# reva.net
KiCad netlist of a schematic drawn in EAGLE
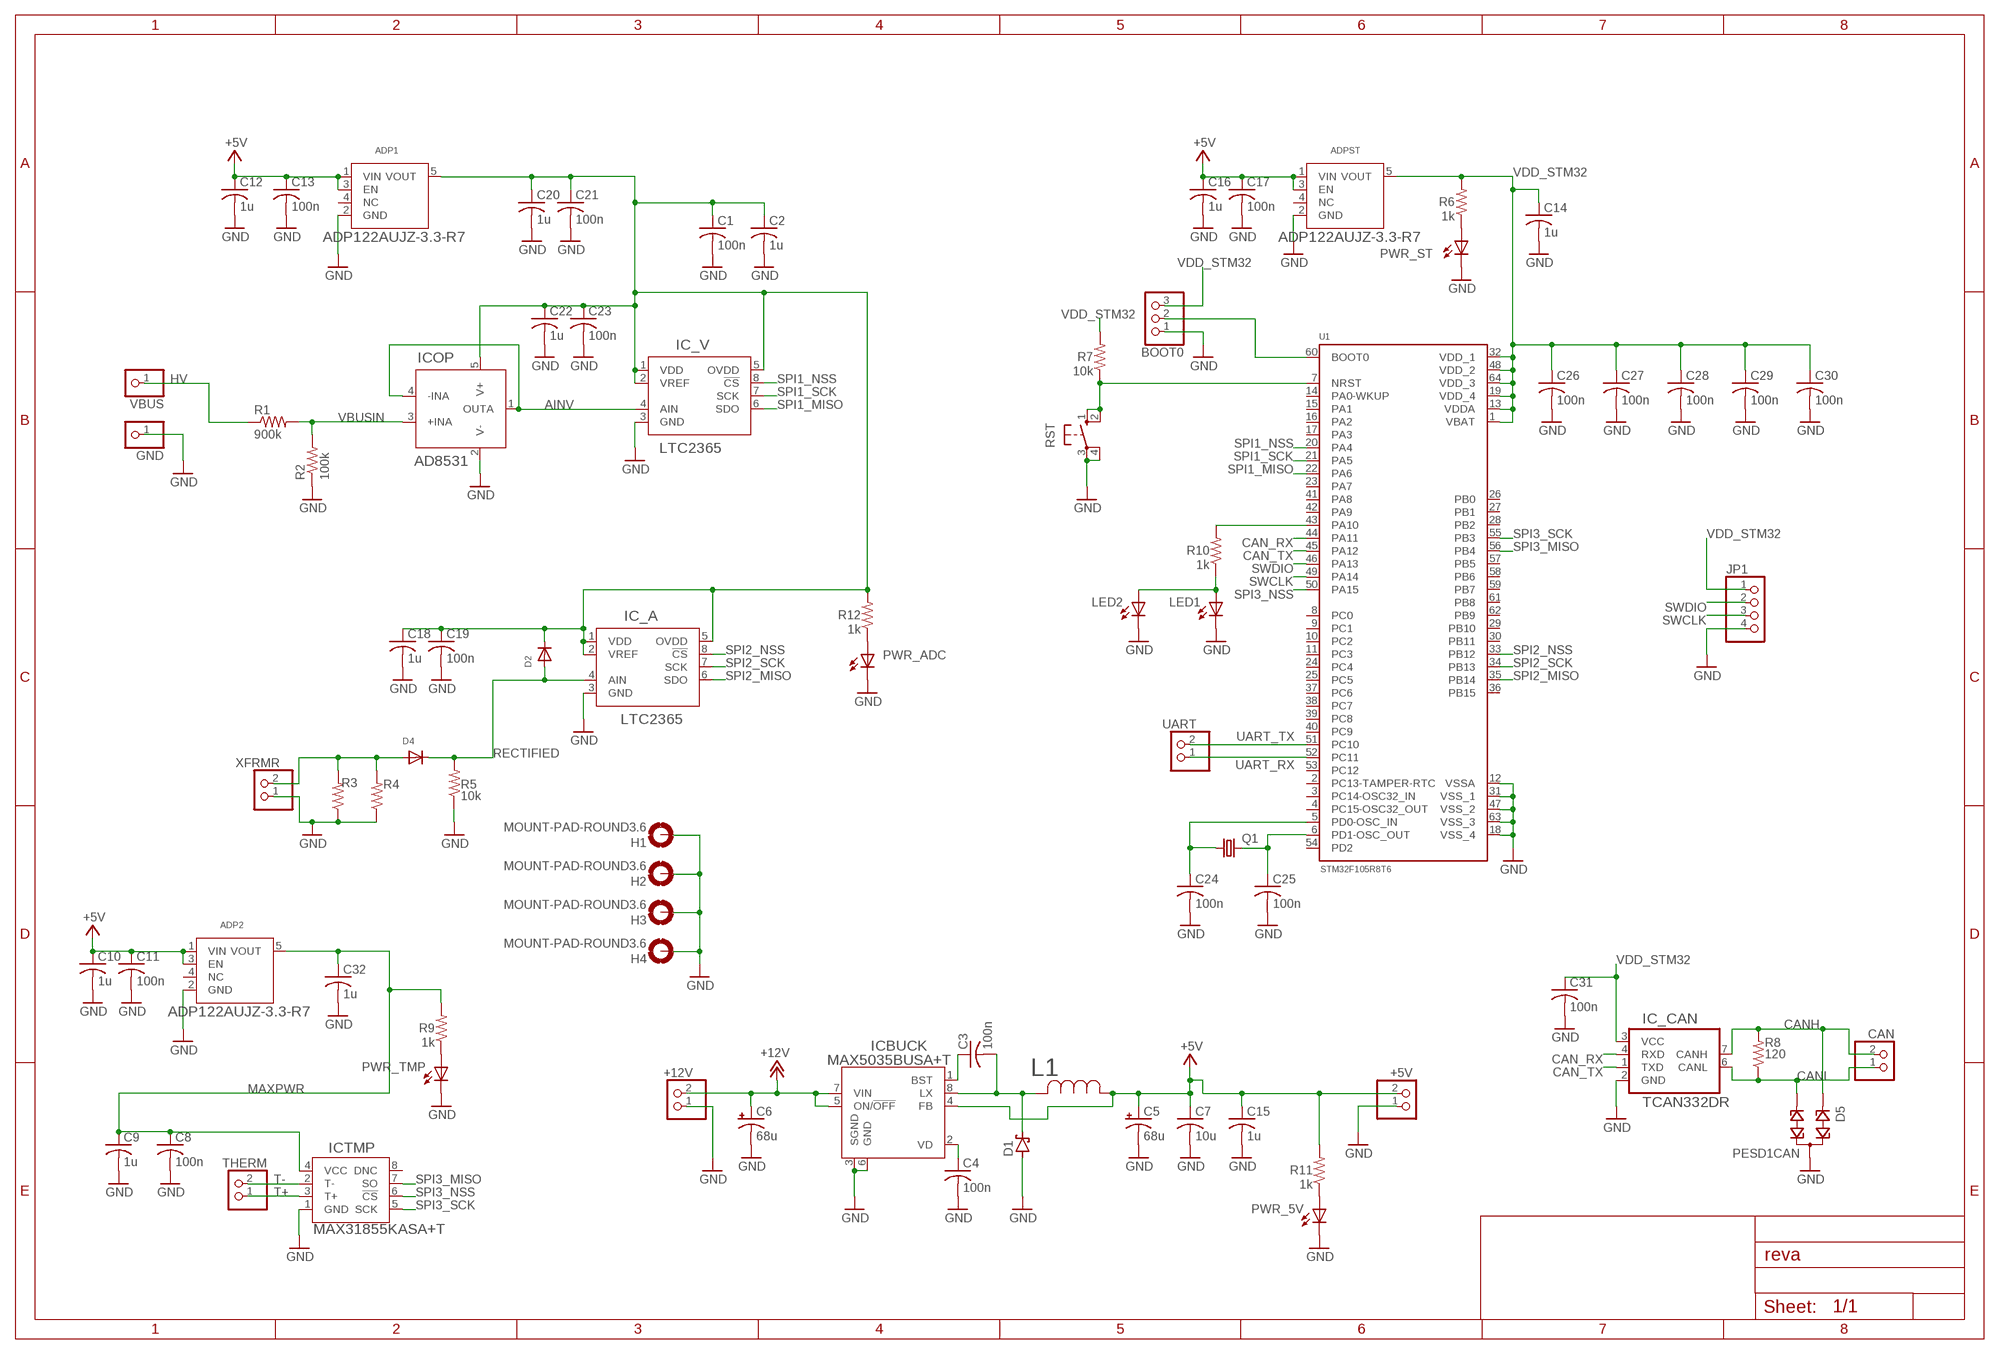
[diagram p0: schematic, sheet 1]

(export (version "E")
  (design (tool "Eeschema 10.0.6"))
  (components
    (comp (ref "+5V")
      (value "PINHD-1X2")
      (footprint "eagle-import:1X02")
      (libsource (lib "eagle-import") (part "PINHD-1X2"))
    )
    (comp (ref "+12V")
      (value "PINHD-1X2")
      (footprint "eagle-import:1X02")
      (libsource (lib "eagle-import") (part "PINHD-1X2"))
    )
    (comp (ref "ADP1")
      (value "ADP122AUJZ-3.3-R7")
      (footprint "eagle-import:SOT95P280X100-5N")
      (libsource (lib "eagle-import") (part "ADP122AUJZ-3.3-R7"))
    )
    (comp (ref "ADP2")
      (value "ADP122AUJZ-3.3-R7")
      (footprint "eagle-import:SOT95P280X100-5N")
      (libsource (lib "eagle-import") (part "ADP122AUJZ-3.3-R7"))
    )
    (comp (ref "ADPST")
      (value "ADP122AUJZ-3.3-R7")
      (footprint "eagle-import:SOT95P280X100-5N")
      (libsource (lib "eagle-import") (part "ADP122AUJZ-3.3-R7"))
    )
    (comp (ref "BOOT0")
      (value "PINHD-1X3")
      (footprint "eagle-import:1X03")
      (libsource (lib "eagle-import") (part "PINHD-1X3"))
    )
    (comp (ref "C1")
      (value "100n")
      (footprint "eagle-import:C0603")
      (libsource (lib "eagle-import") (part "C-USC0603"))
    )
    (comp (ref "C2")
      (value "1u")
      (footprint "eagle-import:C0603")
      (libsource (lib "eagle-import") (part "C-USC0603"))
    )
    (comp (ref "C3")
      (value "100n")
      (footprint "eagle-import:C0603")
      (libsource (lib "eagle-import") (part "C-USC0603"))
    )
    (comp (ref "C4")
      (value "100n")
      (footprint "eagle-import:C0603")
      (libsource (lib "eagle-import") (part "C-USC0603"))
    )
    (comp (ref "C5")
      (value "68u")
      (footprint "eagle-import:E5-8,5")
      (libsource (lib "eagle-import") (part "CPOL-USE5-8.5"))
    )
    (comp (ref "C6")
      (value "68u")
      (footprint "eagle-import:E5-8,5")
      (libsource (lib "eagle-import") (part "CPOL-USE5-8.5"))
    )
    (comp (ref "C7")
      (value "10u")
      (footprint "eagle-import:C0805")
      (libsource (lib "eagle-import") (part "C-USC0805"))
    )
    (comp (ref "C8")
      (value "100n")
      (footprint "eagle-import:C0603")
      (libsource (lib "eagle-import") (part "C-USC0603"))
    )
    (comp (ref "C9")
      (value "1u")
      (footprint "eagle-import:C0603")
      (libsource (lib "eagle-import") (part "C-USC0603"))
    )
    (comp (ref "C10")
      (value "1u")
      (footprint "eagle-import:C0603")
      (libsource (lib "eagle-import") (part "C-USC0603"))
    )
    (comp (ref "C11")
      (value "100n")
      (footprint "eagle-import:C0603")
      (libsource (lib "eagle-import") (part "C-USC0603"))
    )
    (comp (ref "C12")
      (value "1u")
      (footprint "eagle-import:C0603")
      (libsource (lib "eagle-import") (part "C-USC0603"))
    )
    (comp (ref "C13")
      (value "100n")
      (footprint "eagle-import:C0603")
      (libsource (lib "eagle-import") (part "C-USC0603"))
    )
    (comp (ref "C14")
      (value "1u")
      (footprint "eagle-import:C0603")
      (libsource (lib "eagle-import") (part "C-USC0603"))
    )
    (comp (ref "C15")
      (value "1u")
      (footprint "eagle-import:C0603")
      (libsource (lib "eagle-import") (part "C-USC0603"))
    )
    (comp (ref "C16")
      (value "1u")
      (footprint "eagle-import:C0603")
      (libsource (lib "eagle-import") (part "C-USC0603"))
    )
    (comp (ref "C17")
      (value "100n")
      (footprint "eagle-import:C0603")
      (libsource (lib "eagle-import") (part "C-USC0603"))
    )
    (comp (ref "C18")
      (value "1u")
      (footprint "eagle-import:C0603")
      (libsource (lib "eagle-import") (part "C-USC0603"))
    )
    (comp (ref "C19")
      (value "100n")
      (footprint "eagle-import:C0603")
      (libsource (lib "eagle-import") (part "C-USC0603"))
    )
    (comp (ref "C20")
      (value "1u")
      (footprint "eagle-import:C0603")
      (libsource (lib "eagle-import") (part "C-USC0603"))
    )
    (comp (ref "C21")
      (value "100n")
      (footprint "eagle-import:C0603")
      (libsource (lib "eagle-import") (part "C-USC0603"))
    )
    (comp (ref "C22")
      (value "1u")
      (footprint "eagle-import:C0603")
      (libsource (lib "eagle-import") (part "C-USC0603"))
    )
    (comp (ref "C23")
      (value "100n")
      (footprint "eagle-import:C0603")
      (libsource (lib "eagle-import") (part "C-USC0603"))
    )
    (comp (ref "C24")
      (value "100n")
      (footprint "eagle-import:C0603")
      (libsource (lib "eagle-import") (part "C-USC0603"))
    )
    (comp (ref "C25")
      (value "100n")
      (footprint "eagle-import:C0603")
      (libsource (lib "eagle-import") (part "C-USC0603"))
    )
    (comp (ref "C26")
      (value "100n")
      (footprint "eagle-import:C0603")
      (libsource (lib "eagle-import") (part "C-USC0603"))
    )
    (comp (ref "C27")
      (value "100n")
      (footprint "eagle-import:C0603")
      (libsource (lib "eagle-import") (part "C-USC0603"))
    )
    (comp (ref "C28")
      (value "100n")
      (footprint "eagle-import:C0603")
      (libsource (lib "eagle-import") (part "C-USC0603"))
    )
    (comp (ref "C29")
      (value "100n")
      (footprint "eagle-import:C0603")
      (libsource (lib "eagle-import") (part "C-USC0603"))
    )
    (comp (ref "C30")
      (value "100n")
      (footprint "eagle-import:C0603")
      (libsource (lib "eagle-import") (part "C-USC0603"))
    )
    (comp (ref "C31")
      (value "100n")
      (footprint "eagle-import:C0603")
      (libsource (lib "eagle-import") (part "C-USC0603"))
    )
    (comp (ref "C32")
      (value "1u")
      (footprint "eagle-import:C0603")
      (libsource (lib "eagle-import") (part "C-USC0603"))
    )
    (comp (ref "CAN")
      (value "PINHD-1X2")
      (footprint "eagle-import:1X02")
      (libsource (lib "eagle-import") (part "PINHD-1X2"))
    )
    (comp (ref "D1")
      (value "SCHOTTKY-DIODESMD")
      (footprint "eagle-import:SMB")
      (libsource (lib "eagle-import") (part "SCHOTTKY-DIODESMD"))
    )
    (comp (ref "D2")
      (value "DIODESOD-523")
      (footprint "eagle-import:SOD-523")
      (libsource (lib "eagle-import") (part "DIODESOD-523"))
    )
    (comp (ref "D4")
      (value "DIODESOD-523")
      (footprint "eagle-import:SOD-523")
      (libsource (lib "eagle-import") (part "DIODESOD-523"))
    )
    (comp (ref "D5")
      (value "PESD1CAN")
      (footprint "eagle-import:SOT23")
      (libsource (lib "eagle-import") (part "PESD1CAN"))
    )
    (comp (ref "GND")
      (value "PINHD-1X1CB")
      (footprint "eagle-import:1X01-CLEANBIG")
      (libsource (lib "eagle-import") (part "PINHD-1X1CB"))
    )
    (comp (ref "H1")
      (value "MOUNT-PAD-ROUND3.6")
      (footprint "eagle-import:3,6-PAD")
      (libsource (lib "eagle-import") (part "MOUNT-PAD-ROUND3.6"))
    )
    (comp (ref "H2")
      (value "MOUNT-PAD-ROUND3.6")
      (footprint "eagle-import:3,6-PAD")
      (libsource (lib "eagle-import") (part "MOUNT-PAD-ROUND3.6"))
    )
    (comp (ref "H3")
      (value "MOUNT-PAD-ROUND3.6")
      (footprint "eagle-import:3,6-PAD")
      (libsource (lib "eagle-import") (part "MOUNT-PAD-ROUND3.6"))
    )
    (comp (ref "H4")
      (value "MOUNT-PAD-ROUND3.6")
      (footprint "eagle-import:3,6-PAD")
      (libsource (lib "eagle-import") (part "MOUNT-PAD-ROUND3.6"))
    )
    (comp (ref "ICBUCK")
      (value "MAX5035BUSA+T")
      (footprint "eagle-import:21-0041B_8_MXM")
      (fields
        (field (name "MANUFACTURER_PART_NUMBER") "max5035busa+T")
        (field (name "COPYRIGHT") "Copyright (C) 2023 Ultra Librarian. All rights reserved.")
      )
      (libsource (lib "eagle-import") (part "MAX5035BUSA+T"))
    )
    (comp (ref "ICOP")
      (value "AD8531")
      (footprint "eagle-import:RJ_5_ADI")
      (fields
        (field (name "MANUFACTURER_PART_NUMBER") "AD8531ARTZ-REEL7")
        (field (name "COPYRIGHT") "Copyright (C) 2023 Ultra Librarian. All rights reserved.")
      )
      (libsource (lib "eagle-import") (part "AD8531ARTZ-REEL7"))
    )
    (comp (ref "ICTMP")
      (value "MAX31855KASA+T")
      (footprint "eagle-import:21-0041B_8_MXM")
      (fields (field (name "COPYRIGHT") "Copyright (C) 2023 Ultra Librarian. All rights reserved."))
      (libsource (lib "eagle-import") (part "MAX31855KASA+T"))
    )
    (comp (ref "IC_A")
      (value "LTC2365")
      (footprint "eagle-import:TSOT-23_TS8_LIT")
      (fields
        (field (name "MANUFACTURER_PART_NUMBER") "LTC2365ITS8#TRMPBF")
        (field (name "COPYRIGHT") "Copyright (C) 2023 Ultra Librarian. All rights reserved.")
      )
      (libsource (lib "eagle-import") (part "LTC2365ITS8TRMPBF"))
    )
    (comp (ref "IC_CAN")
      (value "TCAN332DR")
      (footprint "eagle-import:SOIC127P599X175-8N")
      (fields (field (name "MF") "Texas Instruments"))
      (libsource (lib "eagle-import") (part "TCAN332DR"))
    )
    (comp (ref "IC_V")
      (value "LTC2365")
      (footprint "eagle-import:TSOT-23_TS8_LIT")
      (fields
        (field (name "MANUFACTURER_PART_NUMBER") "LTC2365ITS8#TRMPBF")
        (field (name "COPYRIGHT") "Copyright (C) 2023 Ultra Librarian. All rights reserved.")
      )
      (libsource (lib "eagle-import") (part "LTC2365ITS8TRMPBF"))
    )
    (comp (ref "JP1")
      (value "PINHD-1X4")
      (footprint "eagle-import:1X04")
      (libsource (lib "eagle-import") (part "PINHD-1X4"))
    )
    (comp (ref "L1")
      (value "IHLP4040DZER101M11")
      (footprint "eagle-import:IND_IHLP-4040DZ_VIS")
      (fields (field (name "COPYRIGHT") "Copyright (C) 2023 Ultra Librarian. All rights reserved."))
      (libsource (lib "eagle-import") (part "IHLP4040DZER101M11"))
    )
    (comp (ref "LED1")
      (value "LED5MM")
      (footprint "eagle-import:LED5MM")
      (libsource (lib "eagle-import") (part "LED5MM"))
    )
    (comp (ref "LED2")
      (value "LEDCHIP-LED0805")
      (footprint "eagle-import:CHIP-LED0805")
      (libsource (lib "eagle-import") (part "LEDCHIP-LED0805"))
    )
    (comp (ref "PWR_5V")
      (value "LEDCHIP-LED0805")
      (footprint "eagle-import:CHIP-LED0805")
      (libsource (lib "eagle-import") (part "LEDCHIP-LED0805"))
    )
    (comp (ref "PWR_ADC")
      (value "LEDCHIP-LED0805")
      (footprint "eagle-import:CHIP-LED0805")
      (libsource (lib "eagle-import") (part "LEDCHIP-LED0805"))
    )
    (comp (ref "PWR_ST")
      (value "LEDCHIP-LED0805")
      (footprint "eagle-import:CHIP-LED0805")
      (libsource (lib "eagle-import") (part "LEDCHIP-LED0805"))
    )
    (comp (ref "PWR_TMP")
      (value "LEDCHIP-LED0805")
      (footprint "eagle-import:CHIP-LED0805")
      (libsource (lib "eagle-import") (part "LEDCHIP-LED0805"))
    )
    (comp (ref "Q1")
      (value "CRYSTALHC49S")
      (footprint "eagle-import:HC49_S")
      (libsource (lib "eagle-import") (part "CRYSTALHC49S"))
    )
    (comp (ref "R1")
      (value "900k")
      (footprint "eagle-import:R0805")
      (libsource (lib "eagle-import") (part "R-US_R0805"))
    )
    (comp (ref "R2")
      (value "100k")
      (footprint "eagle-import:R0805")
      (libsource (lib "eagle-import") (part "R-US_R0805"))
    )
    (comp (ref "R3")
      (value "R-US_R0805")
      (footprint "eagle-import:R0805")
      (libsource (lib "eagle-import") (part "R-US_R0805"))
    )
    (comp (ref "R4")
      (value "R-US_0204/7")
      (footprint "eagle-import:0204_7")
      (libsource (lib "eagle-import") (part "R-US_0204/7"))
    )
    (comp (ref "R5")
      (value "10k")
      (footprint "eagle-import:R0805")
      (libsource (lib "eagle-import") (part "R-US_R0805"))
    )
    (comp (ref "R6")
      (value "1k")
      (footprint "eagle-import:R0805")
      (libsource (lib "eagle-import") (part "R-US_R0805"))
    )
    (comp (ref "R7")
      (value "10k")
      (footprint "eagle-import:R0805")
      (libsource (lib "eagle-import") (part "R-US_R0805"))
    )
    (comp (ref "R8")
      (value "120")
      (footprint "eagle-import:R0805")
      (libsource (lib "eagle-import") (part "R-US_R0805"))
    )
    (comp (ref "R9")
      (value "1k")
      (footprint "eagle-import:R0805")
      (libsource (lib "eagle-import") (part "R-US_R0805"))
    )
    (comp (ref "R10")
      (value "1k")
      (footprint "eagle-import:R0805")
      (libsource (lib "eagle-import") (part "R-US_R0805"))
    )
    (comp (ref "R11")
      (value "1k")
      (footprint "eagle-import:R0805")
      (libsource (lib "eagle-import") (part "R-US_R0805"))
    )
    (comp (ref "R12")
      (value "1k")
      (footprint "eagle-import:R0805")
      (libsource (lib "eagle-import") (part "R-US_R0805"))
    )
    (comp (ref "RST")
      (value "10-XX")
      (footprint "eagle-import:B3F-10XX")
      (fields (field (name "MPN") "B3F-1000"))
      (libsource (lib "eagle-import") (part "10-XX"))
    )
    (comp (ref "THERM")
      (value "PINHD-1X2")
      (footprint "eagle-import:1X02")
      (libsource (lib "eagle-import") (part "PINHD-1X2"))
    )
    (comp (ref "U1")
      (value "STM32F105R8T6")
      (footprint "eagle-import:QFP50P1200X1200X160-64N")
      (fields (field (name "DIGIKEY_PART_NUMBER") "497-8922-ND") (field (name "MF") "STMicroelectronics"))
      (libsource (lib "eagle-import") (part "STM32F105R8T6"))
    )
    (comp (ref "UART")
      (value "PINHD-1X2")
      (footprint "eagle-import:1X02")
      (libsource (lib "eagle-import") (part "PINHD-1X2"))
    )
    (comp (ref "VBUS")
      (value "PINHD-1X1CB")
      (footprint "eagle-import:1X01-CLEANBIG")
      (libsource (lib "eagle-import") (part "PINHD-1X1CB"))
    )
    (comp (ref "XFRMR")
      (value "PINHD-1X2")
      (footprint "eagle-import:1X02")
      (libsource (lib "eagle-import") (part "PINHD-1X2"))
    )
  )
  (nets
    (net (code "1") (name "+5V") (class "Default")
      (node (ref "+5V") (pin "2") (pinfunction "2_2") (pintype "passive"))
      (node (ref "ADP1") (pin "1") (pinfunction "VIN_1") (pintype "power_in"))
      (node (ref "ADP1") (pin "3") (pinfunction "EN_3") (pintype "input"))
      (node (ref "ADP2") (pin "1") (pinfunction "VIN_1") (pintype "power_in"))
      (node (ref "ADP2") (pin "3") (pinfunction "EN_3") (pintype "input"))
      (node (ref "ADPST") (pin "1") (pinfunction "VIN_1") (pintype "power_in"))
      (node (ref "ADPST") (pin "3") (pinfunction "EN_3") (pintype "input"))
      (node (ref "C10") (pin "1") (pinfunction "1_1") (pintype "passive"))
      (node (ref "C11") (pin "1") (pinfunction "1_1") (pintype "passive"))
      (node (ref "C12") (pin "1") (pinfunction "1_1") (pintype "passive"))
      (node (ref "C13") (pin "1") (pinfunction "1_1") (pintype "passive"))
      (node (ref "C15") (pin "1") (pinfunction "1_1") (pintype "passive"))
      (node (ref "C16") (pin "1") (pinfunction "1_1") (pintype "passive"))
      (node (ref "C17") (pin "1") (pinfunction "1_1") (pintype "passive"))
      (node (ref "C5") (pin "+") (pinfunction "+_+") (pintype "passive"))
      (node (ref "C7") (pin "1") (pinfunction "1_1") (pintype "passive"))
      (node (ref "ICBUCK") (pin "4") (pinfunction "FB_4") (pintype "output"))
      (node (ref "L1") (pin "1") (pinfunction "1_1") (pintype "passive"))
      (node (ref "R11") (pin "2") (pinfunction "2_2") (pintype "passive"))
    )
    (net (code "2") (name "+12V") (class "Default")
      (node (ref "+12V") (pin "2") (pinfunction "2_2") (pintype "passive"))
      (node (ref "C6") (pin "+") (pinfunction "+_+") (pintype "passive"))
      (node (ref "ICBUCK") (pin "5") (pinfunction "ON/~{OFF}_5") (pintype "input"))
      (node (ref "ICBUCK") (pin "7") (pinfunction "VIN_7") (pintype "power_in"))
    )
    (net (code "3") (name "/AINV") (class "Default")
      (node (ref "ICOP") (pin "1") (pinfunction "OUTA_1") (pintype "passive"))
      (node (ref "ICOP") (pin "4") (pinfunction "-INA_4") (pintype "power_in"))
      (node (ref "IC_V") (pin "4") (pinfunction "AIN_4") (pintype "input"))
    )
    (net (code "4") (name "/CANH") (class "Default")
      (node (ref "CAN") (pin "2") (pinfunction "2_2") (pintype "passive"))
      (node (ref "D5") (pin "1") (pinfunction "1_1") (pintype "passive"))
      (node (ref "IC_CAN") (pin "7") (pinfunction "CANH_7") (pintype "bidirectional"))
      (node (ref "R8") (pin "2") (pinfunction "2_2") (pintype "passive"))
    )
    (net (code "5") (name "/CANL") (class "Default")
      (node (ref "CAN") (pin "1") (pinfunction "1_1") (pintype "passive"))
      (node (ref "D5") (pin "2") (pinfunction "2_2") (pintype "passive"))
      (node (ref "IC_CAN") (pin "6") (pinfunction "CANL_6") (pintype "bidirectional"))
      (node (ref "R8") (pin "1") (pinfunction "1_1") (pintype "passive"))
    )
    (net (code "6") (name "/CAN_RX") (class "Default")
      (node (ref "IC_CAN") (pin "4") (pinfunction "RXD_4") (pintype "bidirectional"))
      (node (ref "U1") (pin "44") (pinfunction "PA11_44") (pintype "bidirectional"))
    )
    (net (code "7") (name "/CAN_TX") (class "Default")
      (node (ref "IC_CAN") (pin "1") (pinfunction "TXD_1") (pintype "bidirectional"))
      (node (ref "U1") (pin "45") (pinfunction "PA12_45") (pintype "bidirectional"))
    )
    (net (code "8") (name "/HV") (class "Default")
      (node (ref "R1") (pin "1") (pinfunction "1_1") (pintype "passive"))
      (node (ref "VBUS") (pin "1") (pinfunction "1_1") (pintype "passive"))
    )
    (net (code "9") (name "/MAXPWR") (class "Default")
      (node (ref "ADP2") (pin "5") (pinfunction "VOUT_5") (pintype "output"))
      (node (ref "C32") (pin "1") (pinfunction "1_1") (pintype "passive"))
      (node (ref "C8") (pin "1") (pinfunction "1_1") (pintype "passive"))
      (node (ref "C9") (pin "1") (pinfunction "1_1") (pintype "passive"))
      (node (ref "ICTMP") (pin "4") (pinfunction "VCC_4") (pintype "power_in"))
      (node (ref "R9") (pin "2") (pinfunction "2_2") (pintype "passive"))
    )
    (net (code "10") (name "/RECTIFIED") (class "Default")
      (node (ref "D2") (pin "A") (pinfunction "A_A") (pintype "passive"))
      (node (ref "D4") (pin "K") (pinfunction "C_K") (pintype "passive"))
      (node (ref "IC_A") (pin "4") (pinfunction "AIN_4") (pintype "input"))
      (node (ref "R5") (pin "2") (pinfunction "2_2") (pintype "passive"))
    )
    (net (code "11") (name "/SPI1_MISO") (class "Default")
      (node (ref "IC_V") (pin "6") (pinfunction "SDO_6") (pintype "output"))
      (node (ref "U1") (pin "22") (pinfunction "PA6_22") (pintype "bidirectional"))
    )
    (net (code "12") (name "/SPI1_NSS") (class "Default")
      (node (ref "IC_V") (pin "8") (pinfunction "~{CS}_8") (pintype "input"))
      (node (ref "U1") (pin "20") (pinfunction "PA4_20") (pintype "bidirectional"))
    )
    (net (code "13") (name "/SPI1_SCK") (class "Default")
      (node (ref "IC_V") (pin "7") (pinfunction "SCK_7") (pintype "input"))
      (node (ref "U1") (pin "21") (pinfunction "PA5_21") (pintype "bidirectional"))
    )
    (net (code "14") (name "/SPI2_MISO") (class "Default")
      (node (ref "IC_A") (pin "6") (pinfunction "SDO_6") (pintype "output"))
      (node (ref "U1") (pin "35") (pinfunction "PB14_35") (pintype "bidirectional"))
    )
    (net (code "15") (name "/SPI2_NSS") (class "Default")
      (node (ref "IC_A") (pin "8") (pinfunction "~{CS}_8") (pintype "input"))
      (node (ref "U1") (pin "33") (pinfunction "PB12_33") (pintype "bidirectional"))
    )
    (net (code "16") (name "/SPI2_SCK") (class "Default")
      (node (ref "IC_A") (pin "7") (pinfunction "SCK_7") (pintype "input"))
      (node (ref "U1") (pin "34") (pinfunction "PB13_34") (pintype "bidirectional"))
    )
    (net (code "17") (name "/SPI3_MISO") (class "Default")
      (node (ref "ICTMP") (pin "7") (pinfunction "SO_7") (pintype "output"))
      (node (ref "U1") (pin "56") (pinfunction "PB4_56") (pintype "bidirectional"))
    )
    (net (code "18") (name "/SPI3_NSS") (class "Default")
      (node (ref "ICTMP") (pin "6") (pinfunction "~{CS}_6") (pintype "passive"))
      (node (ref "U1") (pin "50") (pinfunction "PA15_50") (pintype "bidirectional"))
    )
    (net (code "19") (name "/SPI3_SCK") (class "Default")
      (node (ref "ICTMP") (pin "5") (pinfunction "SCK_5") (pintype "input"))
      (node (ref "U1") (pin "55") (pinfunction "PB3_55") (pintype "bidirectional"))
    )
    (net (code "20") (name "/SWCLK") (class "Default")
      (node (ref "JP1") (pin "3") (pinfunction "3_3") (pintype "passive"))
      (node (ref "U1") (pin "49") (pinfunction "PA14_49") (pintype "bidirectional"))
    )
    (net (code "21") (name "/SWDIO") (class "Default")
      (node (ref "JP1") (pin "2") (pinfunction "2_2") (pintype "passive"))
      (node (ref "U1") (pin "46") (pinfunction "PA13_46") (pintype "bidirectional"))
    )
    (net (code "22") (name "/T+") (class "Default")
      (node (ref "ICTMP") (pin "3") (pinfunction "T+_3") (pintype "input"))
      (node (ref "THERM") (pin "1") (pinfunction "1_1") (pintype "passive"))
    )
    (net (code "23") (name "/T-") (class "Default")
      (node (ref "ICTMP") (pin "2") (pinfunction "T-_2") (pintype "input"))
      (node (ref "THERM") (pin "2") (pinfunction "2_2") (pintype "passive"))
    )
    (net (code "24") (name "/UART_RX") (class "Default")
      (node (ref "U1") (pin "52") (pinfunction "PC11_52") (pintype "bidirectional"))
      (node (ref "UART") (pin "1") (pinfunction "1_1") (pintype "passive"))
    )
    (net (code "25") (name "/UART_TX") (class "Default")
      (node (ref "U1") (pin "51") (pinfunction "PC10_51") (pintype "bidirectional"))
      (node (ref "UART") (pin "2") (pinfunction "2_2") (pintype "passive"))
    )
    (net (code "26") (name "/VBUSIN") (class "Default")
      (node (ref "ICOP") (pin "3") (pinfunction "+INA_3") (pintype "power_in"))
      (node (ref "R1") (pin "2") (pinfunction "2_2") (pintype "passive"))
      (node (ref "R2") (pin "2") (pinfunction "2_2") (pintype "passive"))
    )
    (net (code "27") (name "/VDD_STM32") (class "Default")
      (node (ref "ADPST") (pin "5") (pinfunction "VOUT_5") (pintype "output"))
      (node (ref "BOOT0") (pin "3") (pinfunction "3_3") (pintype "passive"))
      (node (ref "C14") (pin "1") (pinfunction "1_1") (pintype "passive"))
      (node (ref "C26") (pin "1") (pinfunction "1_1") (pintype "passive"))
      (node (ref "C27") (pin "1") (pinfunction "1_1") (pintype "passive"))
      (node (ref "C28") (pin "1") (pinfunction "1_1") (pintype "passive"))
      (node (ref "C29") (pin "1") (pinfunction "1_1") (pintype "passive"))
      (node (ref "C30") (pin "1") (pinfunction "1_1") (pintype "passive"))
      (node (ref "C31") (pin "1") (pinfunction "1_1") (pintype "passive"))
      (node (ref "IC_CAN") (pin "3") (pinfunction "VCC_3") (pintype "power_in"))
      (node (ref "JP1") (pin "1") (pinfunction "1_1") (pintype "passive"))
      (node (ref "R6") (pin "2") (pinfunction "2_2") (pintype "passive"))
      (node (ref "R7") (pin "2") (pinfunction "2_2") (pintype "passive"))
      (node (ref "U1") (pin "1") (pinfunction "VBAT_1") (pintype "power_in"))
      (node (ref "U1") (pin "13") (pinfunction "VDDA_13") (pintype "power_in"))
      (node (ref "U1") (pin "19") (pinfunction "VDD_4_19") (pintype "power_in"))
      (node (ref "U1") (pin "32") (pinfunction "VDD_1_32") (pintype "power_in"))
      (node (ref "U1") (pin "48") (pinfunction "VDD_2_48") (pintype "power_in"))
      (node (ref "U1") (pin "64") (pinfunction "VDD_3_64") (pintype "power_in"))
    )
    (net (code "28") (name "GND") (class "Default")
      (node (ref "+12V") (pin "1") (pinfunction "1_1") (pintype "passive"))
      (node (ref "+5V") (pin "1") (pinfunction "1_1") (pintype "passive"))
      (node (ref "ADP1") (pin "2") (pinfunction "GND_2") (pintype "passive"))
      (node (ref "ADP2") (pin "2") (pinfunction "GND_2") (pintype "passive"))
      (node (ref "ADPST") (pin "2") (pinfunction "GND_2") (pintype "passive"))
      (node (ref "BOOT0") (pin "1") (pinfunction "1_1") (pintype "passive"))
      (node (ref "C1") (pin "2") (pinfunction "2_2") (pintype "passive"))
      (node (ref "C10") (pin "2") (pinfunction "2_2") (pintype "passive"))
      (node (ref "C11") (pin "2") (pinfunction "2_2") (pintype "passive"))
      (node (ref "C12") (pin "2") (pinfunction "2_2") (pintype "passive"))
      (node (ref "C13") (pin "2") (pinfunction "2_2") (pintype "passive"))
      (node (ref "C14") (pin "2") (pinfunction "2_2") (pintype "passive"))
      (node (ref "C15") (pin "2") (pinfunction "2_2") (pintype "passive"))
      (node (ref "C16") (pin "2") (pinfunction "2_2") (pintype "passive"))
      (node (ref "C17") (pin "2") (pinfunction "2_2") (pintype "passive"))
      (node (ref "C18") (pin "2") (pinfunction "2_2") (pintype "passive"))
      (node (ref "C19") (pin "2") (pinfunction "2_2") (pintype "passive"))
      (node (ref "C2") (pin "2") (pinfunction "2_2") (pintype "passive"))
      (node (ref "C20") (pin "2") (pinfunction "2_2") (pintype "passive"))
      (node (ref "C21") (pin "2") (pinfunction "2_2") (pintype "passive"))
      (node (ref "C22") (pin "2") (pinfunction "2_2") (pintype "passive"))
      (node (ref "C23") (pin "2") (pinfunction "2_2") (pintype "passive"))
      (node (ref "C24") (pin "2") (pinfunction "2_2") (pintype "passive"))
      (node (ref "C25") (pin "2") (pinfunction "2_2") (pintype "passive"))
      (node (ref "C26") (pin "2") (pinfunction "2_2") (pintype "passive"))
      (node (ref "C27") (pin "2") (pinfunction "2_2") (pintype "passive"))
      (node (ref "C28") (pin "2") (pinfunction "2_2") (pintype "passive"))
      (node (ref "C29") (pin "2") (pinfunction "2_2") (pintype "passive"))
      (node (ref "C30") (pin "2") (pinfunction "2_2") (pintype "passive"))
      (node (ref "C31") (pin "2") (pinfunction "2_2") (pintype "passive"))
      (node (ref "C32") (pin "2") (pinfunction "2_2") (pintype "passive"))
      (node (ref "C4") (pin "2") (pinfunction "2_2") (pintype "passive"))
      (node (ref "C5") (pin "-") (pinfunction "-_-") (pintype "passive"))
      (node (ref "C6") (pin "-") (pinfunction "-_-") (pintype "passive"))
      (node (ref "C7") (pin "2") (pinfunction "2_2") (pintype "passive"))
      (node (ref "C8") (pin "2") (pinfunction "2_2") (pintype "passive"))
      (node (ref "C9") (pin "2") (pinfunction "2_2") (pintype "passive"))
      (node (ref "D1") (pin "A") (pinfunction "A_A") (pintype "passive"))
      (node (ref "D5") (pin "3") (pinfunction "3_3") (pintype "passive"))
      (node (ref "GND") (pin "1") (pinfunction "1_1") (pintype "passive"))
      (node (ref "H1") (pin "B3,6") (pinfunction "MOUNT_B3,6") (pintype "passive"))
      (node (ref "H2") (pin "B3,6") (pinfunction "MOUNT_B3,6") (pintype "passive"))
      (node (ref "H3") (pin "B3,6") (pinfunction "MOUNT_B3,6") (pintype "passive"))
      (node (ref "H4") (pin "B3,6") (pinfunction "MOUNT_B3,6") (pintype "passive"))
      (node (ref "ICBUCK") (pin "3") (pinfunction "SGND_3") (pintype "power_in"))
      (node (ref "ICBUCK") (pin "6") (pinfunction "GND_6") (pintype "power_in"))
      (node (ref "ICOP") (pin "2") (pinfunction "V-_2") (pintype "passive"))
      (node (ref "ICTMP") (pin "1") (pinfunction "GND_1") (pintype "power_in"))
      (node (ref "IC_A") (pin "3") (pinfunction "GND_3") (pintype "power_in"))
      (node (ref "IC_CAN") (pin "2") (pinfunction "GND_2") (pintype "power_in"))
      (node (ref "IC_V") (pin "3") (pinfunction "GND_3") (pintype "power_in"))
      (node (ref "JP1") (pin "4") (pinfunction "4_4") (pintype "passive"))
      (node (ref "LED1") (pin "K") (pinfunction "C_K") (pintype "passive"))
      (node (ref "LED2") (pin "C") (pinfunction "C_C") (pintype "passive"))
      (node (ref "PWR_5V") (pin "C") (pinfunction "C_C") (pintype "passive"))
      (node (ref "PWR_ADC") (pin "C") (pinfunction "C_C") (pintype "passive"))
      (node (ref "PWR_ST") (pin "C") (pinfunction "C_C") (pintype "passive"))
      (node (ref "PWR_TMP") (pin "C") (pinfunction "C_C") (pintype "passive"))
      (node (ref "R2") (pin "1") (pinfunction "1_1") (pintype "passive"))
      (node (ref "R3") (pin "1") (pinfunction "1_1") (pintype "passive"))
      (node (ref "R4") (pin "1") (pinfunction "1_1") (pintype "passive"))
      (node (ref "R5") (pin "1") (pinfunction "1_1") (pintype "passive"))
      (node (ref "RST") (pin "3") (pinfunction "P_3") (pintype "passive"))
      (node (ref "RST") (pin "4") (pinfunction "P1_4") (pintype "passive"))
      (node (ref "U1") (pin "12") (pinfunction "VSSA_12") (pintype "power_in"))
      (node (ref "U1") (pin "18") (pinfunction "VSS_4_18") (pintype "power_in"))
      (node (ref "U1") (pin "31") (pinfunction "VSS_1_31") (pintype "power_in"))
      (node (ref "U1") (pin "47") (pinfunction "VSS_2_47") (pintype "power_in"))
      (node (ref "U1") (pin "63") (pinfunction "VSS_3_63") (pintype "power_in"))
      (node (ref "XFRMR") (pin "1") (pinfunction "1_1") (pintype "passive"))
    )
    (net (code "29") (name "Net-(ADP1-VOUT)") (class "Default")
      (node (ref "ADP1") (pin "5") (pinfunction "VOUT_5") (pintype "output"))
      (node (ref "C1") (pin "1") (pinfunction "1_1") (pintype "passive"))
      (node (ref "C18") (pin "1") (pinfunction "1_1") (pintype "passive"))
      (node (ref "C19") (pin "1") (pinfunction "1_1") (pintype "passive"))
      (node (ref "C2") (pin "1") (pinfunction "1_1") (pintype "passive"))
      (node (ref "C20") (pin "1") (pinfunction "1_1") (pintype "passive"))
      (node (ref "C21") (pin "1") (pinfunction "1_1") (pintype "passive"))
      (node (ref "C22") (pin "1") (pinfunction "1_1") (pintype "passive"))
      (node (ref "C23") (pin "1") (pinfunction "1_1") (pintype "passive"))
      (node (ref "D2") (pin "K") (pinfunction "C_K") (pintype "passive"))
      (node (ref "ICOP") (pin "5") (pinfunction "V+_5") (pintype "passive"))
      (node (ref "IC_A") (pin "1") (pinfunction "VDD_1") (pintype "power_in"))
      (node (ref "IC_A") (pin "2") (pinfunction "VREF_2") (pintype "input"))
      (node (ref "IC_A") (pin "5") (pinfunction "OVDD_5") (pintype "power_in"))
      (node (ref "IC_V") (pin "1") (pinfunction "VDD_1") (pintype "power_in"))
      (node (ref "IC_V") (pin "2") (pinfunction "VREF_2") (pintype "input"))
      (node (ref "IC_V") (pin "5") (pinfunction "OVDD_5") (pintype "power_in"))
      (node (ref "R12") (pin "2") (pinfunction "2_2") (pintype "passive"))
    )
    (net (code "30") (name "Net-(D4-PadA)") (class "Default")
      (node (ref "D4") (pin "A") (pinfunction "A_A") (pintype "passive"))
      (node (ref "R3") (pin "2") (pinfunction "2_2") (pintype "passive"))
      (node (ref "R4") (pin "2") (pinfunction "2_2") (pintype "passive"))
      (node (ref "XFRMR") (pin "2") (pinfunction "2_2") (pintype "passive"))
    )
    (net (code "31") (name "Net-(ICBUCK-BST)") (class "Default")
      (node (ref "C3") (pin "1") (pinfunction "1_1") (pintype "passive"))
      (node (ref "ICBUCK") (pin "1") (pinfunction "BST_1") (pintype "passive"))
    )
    (net (code "32") (name "Net-(ICBUCK-LX)") (class "Default")
      (node (ref "C3") (pin "2") (pinfunction "2_2") (pintype "passive"))
      (node (ref "D1") (pin "C") (pinfunction "C_C") (pintype "passive"))
      (node (ref "ICBUCK") (pin "8") (pinfunction "LX_8") (pintype "passive"))
      (node (ref "L1") (pin "2") (pinfunction "2_2") (pintype "passive"))
    )
    (net (code "33") (name "Net-(ICBUCK-VD)") (class "Default")
      (node (ref "C4") (pin "1") (pinfunction "1_1") (pintype "passive"))
      (node (ref "ICBUCK") (pin "2") (pinfunction "VD_2") (pintype "power_in"))
    )
    (net (code "34") (name "Net-(LED1-PadA)") (class "Default")
      (node (ref "LED1") (pin "A") (pinfunction "A_A") (pintype "passive"))
      (node (ref "LED2") (pin "A") (pinfunction "A_A") (pintype "passive"))
      (node (ref "R10") (pin "1") (pinfunction "1_1") (pintype "passive"))
    )
    (net (code "35") (name "Net-(PWR_5V-PadA)") (class "Default")
      (node (ref "PWR_5V") (pin "A") (pinfunction "A_A") (pintype "passive"))
      (node (ref "R11") (pin "1") (pinfunction "1_1") (pintype "passive"))
    )
    (net (code "36") (name "Net-(PWR_ADC-PadA)") (class "Default")
      (node (ref "PWR_ADC") (pin "A") (pinfunction "A_A") (pintype "passive"))
      (node (ref "R12") (pin "1") (pinfunction "1_1") (pintype "passive"))
    )
    (net (code "37") (name "Net-(PWR_ST-PadA)") (class "Default")
      (node (ref "PWR_ST") (pin "A") (pinfunction "A_A") (pintype "passive"))
      (node (ref "R6") (pin "1") (pinfunction "1_1") (pintype "passive"))
    )
    (net (code "38") (name "Net-(PWR_TMP-PadA)") (class "Default")
      (node (ref "PWR_TMP") (pin "A") (pinfunction "A_A") (pintype "passive"))
      (node (ref "R9") (pin "1") (pinfunction "1_1") (pintype "passive"))
    )
    (net (code "39") (name "Net-(RST-S)") (class "Default")
      (node (ref "R7") (pin "1") (pinfunction "1_1") (pintype "passive"))
      (node (ref "RST") (pin "1") (pinfunction "S_1") (pintype "passive"))
      (node (ref "RST") (pin "2") (pinfunction "S1_2") (pintype "passive"))
      (node (ref "U1") (pin "7") (pinfunction "NRST_7") (pintype "bidirectional"))
    )
    (net (code "40") (name "Net-(U1-BOOT0)") (class "Default")
      (node (ref "BOOT0") (pin "2") (pinfunction "2_2") (pintype "passive"))
      (node (ref "U1") (pin "60") (pinfunction "BOOT0_60") (pintype "input"))
    )
    (net (code "41") (name "Net-(U1-PA10)") (class "Default")
      (node (ref "R10") (pin "2") (pinfunction "2_2") (pintype "passive"))
      (node (ref "U1") (pin "43") (pinfunction "PA10_43") (pintype "bidirectional"))
    )
    (net (code "42") (name "Net-(U1-PD0-OSC_IN)") (class "Default")
      (node (ref "C24") (pin "1") (pinfunction "1_1") (pintype "passive"))
      (node (ref "Q1") (pin "1") (pinfunction "1_1") (pintype "passive"))
      (node (ref "U1") (pin "5") (pinfunction "PD0-OSC_IN_5") (pintype "bidirectional"))
    )
    (net (code "43") (name "Net-(U1-PD1-OSC_OUT)") (class "Default")
      (node (ref "C25") (pin "1") (pinfunction "1_1") (pintype "passive"))
      (node (ref "Q1") (pin "2") (pinfunction "2_2") (pintype "passive"))
      (node (ref "U1") (pin "6") (pinfunction "PD1-OSC_OUT_6") (pintype "bidirectional"))
    )
    (net (code "44") (name "unconnected-(ADP1-NC-Pad4)") (class "Default")
      (node (ref "ADP1") (pin "4") (pinfunction "NC_4") (pintype "input"))
    )
    (net (code "45") (name "unconnected-(ADP2-NC-Pad4)") (class "Default")
      (node (ref "ADP2") (pin "4") (pinfunction "NC_4") (pintype "input"))
    )
    (net (code "46") (name "unconnected-(ADPST-NC-Pad4)") (class "Default")
      (node (ref "ADPST") (pin "4") (pinfunction "NC_4") (pintype "input"))
    )
    (net (code "47") (name "unconnected-(ICTMP-DNC-Pad8)") (class "Default")
      (node (ref "ICTMP") (pin "8") (pinfunction "DNC_8") (pintype "no_connect"))
    )
    (net (code "48") (name "unconnected-(U1-PA0-WKUP-Pad14)") (class "Default")
      (node (ref "U1") (pin "14") (pinfunction "PA0-WKUP_14") (pintype "bidirectional"))
    )
    (net (code "49") (name "unconnected-(U1-PA1-Pad15)") (class "Default")
      (node (ref "U1") (pin "15") (pinfunction "PA1_15") (pintype "bidirectional"))
    )
    (net (code "50") (name "unconnected-(U1-PA2-Pad16)") (class "Default")
      (node (ref "U1") (pin "16") (pinfunction "PA2_16") (pintype "bidirectional"))
    )
    (net (code "51") (name "unconnected-(U1-PA3-Pad17)") (class "Default")
      (node (ref "U1") (pin "17") (pinfunction "PA3_17") (pintype "bidirectional"))
    )
    (net (code "52") (name "unconnected-(U1-PA7-Pad23)") (class "Default")
      (node (ref "U1") (pin "23") (pinfunction "PA7_23") (pintype "bidirectional"))
    )
    (net (code "53") (name "unconnected-(U1-PA8-Pad41)") (class "Default")
      (node (ref "U1") (pin "41") (pinfunction "PA8_41") (pintype "bidirectional"))
    )
    (net (code "54") (name "unconnected-(U1-PA9-Pad42)") (class "Default")
      (node (ref "U1") (pin "42") (pinfunction "PA9_42") (pintype "bidirectional"))
    )
    (net (code "55") (name "unconnected-(U1-PB0-Pad26)") (class "Default")
      (node (ref "U1") (pin "26") (pinfunction "PB0_26") (pintype "bidirectional"))
    )
    (net (code "56") (name "unconnected-(U1-PB1-Pad27)") (class "Default")
      (node (ref "U1") (pin "27") (pinfunction "PB1_27") (pintype "bidirectional"))
    )
    (net (code "57") (name "unconnected-(U1-PB2-Pad28)") (class "Default")
      (node (ref "U1") (pin "28") (pinfunction "PB2_28") (pintype "bidirectional"))
    )
    (net (code "58") (name "unconnected-(U1-PB5-Pad57)") (class "Default")
      (node (ref "U1") (pin "57") (pinfunction "PB5_57") (pintype "bidirectional"))
    )
    (net (code "59") (name "unconnected-(U1-PB6-Pad58)") (class "Default")
      (node (ref "U1") (pin "58") (pinfunction "PB6_58") (pintype "bidirectional"))
    )
    (net (code "60") (name "unconnected-(U1-PB7-Pad59)") (class "Default")
      (node (ref "U1") (pin "59") (pinfunction "PB7_59") (pintype "bidirectional"))
    )
    (net (code "61") (name "unconnected-(U1-PB8-Pad61)") (class "Default")
      (node (ref "U1") (pin "61") (pinfunction "PB8_61") (pintype "bidirectional"))
    )
    (net (code "62") (name "unconnected-(U1-PB9-Pad62)") (class "Default")
      (node (ref "U1") (pin "62") (pinfunction "PB9_62") (pintype "bidirectional"))
    )
    (net (code "63") (name "unconnected-(U1-PB10-Pad29)") (class "Default")
      (node (ref "U1") (pin "29") (pinfunction "PB10_29") (pintype "bidirectional"))
    )
    (net (code "64") (name "unconnected-(U1-PB11-Pad30)") (class "Default")
      (node (ref "U1") (pin "30") (pinfunction "PB11_30") (pintype "bidirectional"))
    )
    (net (code "65") (name "unconnected-(U1-PB15-Pad36)") (class "Default")
      (node (ref "U1") (pin "36") (pinfunction "PB15_36") (pintype "bidirectional"))
    )
    (net (code "66") (name "unconnected-(U1-PC0-Pad8)") (class "Default")
      (node (ref "U1") (pin "8") (pinfunction "PC0_8") (pintype "bidirectional"))
    )
    (net (code "67") (name "unconnected-(U1-PC1-Pad9)") (class "Default")
      (node (ref "U1") (pin "9") (pinfunction "PC1_9") (pintype "bidirectional"))
    )
    (net (code "68") (name "unconnected-(U1-PC2-Pad10)") (class "Default")
      (node (ref "U1") (pin "10") (pinfunction "PC2_10") (pintype "bidirectional"))
    )
    (net (code "69") (name "unconnected-(U1-PC3-Pad11)") (class "Default")
      (node (ref "U1") (pin "11") (pinfunction "PC3_11") (pintype "bidirectional"))
    )
    (net (code "70") (name "unconnected-(U1-PC4-Pad24)") (class "Default")
      (node (ref "U1") (pin "24") (pinfunction "PC4_24") (pintype "bidirectional"))
    )
    (net (code "71") (name "unconnected-(U1-PC5-Pad25)") (class "Default")
      (node (ref "U1") (pin "25") (pinfunction "PC5_25") (pintype "bidirectional"))
    )
    (net (code "72") (name "unconnected-(U1-PC6-Pad37)") (class "Default")
      (node (ref "U1") (pin "37") (pinfunction "PC6_37") (pintype "bidirectional"))
    )
    (net (code "73") (name "unconnected-(U1-PC7-Pad38)") (class "Default")
      (node (ref "U1") (pin "38") (pinfunction "PC7_38") (pintype "bidirectional"))
    )
    (net (code "74") (name "unconnected-(U1-PC8-Pad39)") (class "Default")
      (node (ref "U1") (pin "39") (pinfunction "PC8_39") (pintype "bidirectional"))
    )
    (net (code "75") (name "unconnected-(U1-PC9-Pad40)") (class "Default")
      (node (ref "U1") (pin "40") (pinfunction "PC9_40") (pintype "bidirectional"))
    )
    (net (code "76") (name "unconnected-(U1-PC12-Pad53)") (class "Default")
      (node (ref "U1") (pin "53") (pinfunction "PC12_53") (pintype "bidirectional"))
    )
    (net (code "77") (name "unconnected-(U1-PC13-TAMPER-RTC-Pad2)") (class "Default")
      (node (ref "U1") (pin "2") (pinfunction "PC13-TAMPER-RTC_2") (pintype "bidirectional"))
    )
    (net (code "78") (name "unconnected-(U1-PC14-OSC32_IN-Pad3)") (class "Default")
      (node (ref "U1") (pin "3") (pinfunction "PC14-OSC32_IN_3") (pintype "bidirectional"))
    )
    (net (code "79") (name "unconnected-(U1-PC15-OSC32_OUT-Pad4)") (class "Default")
      (node (ref "U1") (pin "4") (pinfunction "PC15-OSC32_OUT_4") (pintype "bidirectional"))
    )
    (net (code "80") (name "unconnected-(U1-PD2-Pad54)") (class "Default")
      (node (ref "U1") (pin "54") (pinfunction "PD2_54") (pintype "bidirectional"))
    )
  )
)
